# interacto.net
KiCad netlist of a schematic drawn in EAGLE
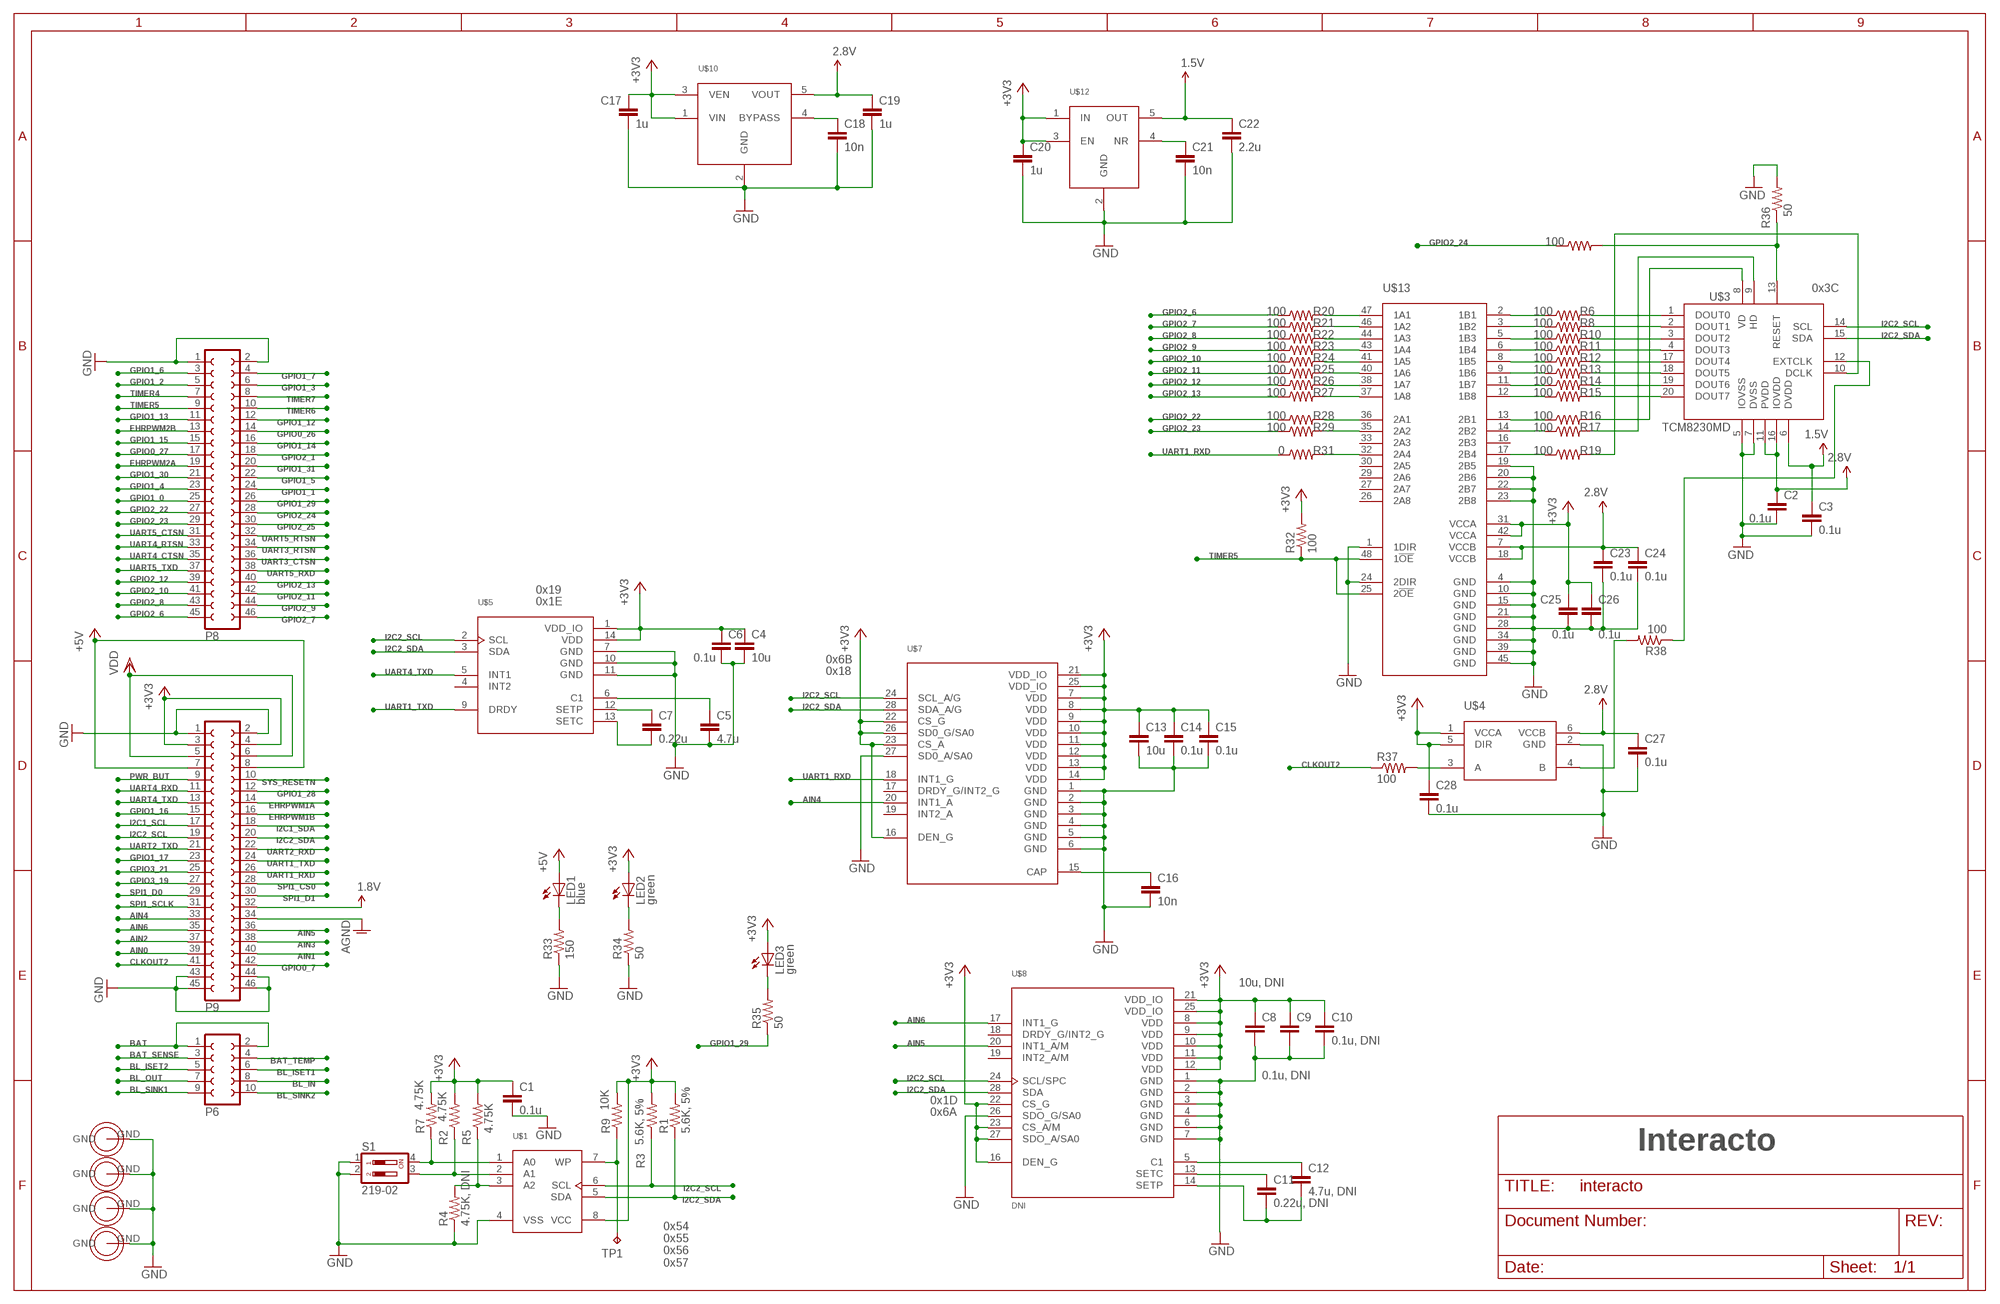
[diagram p0: schematic, sheet 1]

(export (version "E")
  (design (tool "Eeschema 10.0.6"))
  (components
    (comp (ref "C1")
      (value "0.1u")
      (footprint "eagle-import:C0603")
      (fields (field (name "MPN") "VJ0603V104ZXXCW1BC"))
      (libsource (lib "eagle-import") (part "C-EUC0603"))
    )
    (comp (ref "C2")
      (value "0.1u")
      (footprint "eagle-import:C0603")
      (fields (field (name "MPN") "VJ0603V104ZXXCW1BC"))
      (libsource (lib "eagle-import") (part "C-EUC0603"))
    )
    (comp (ref "C3")
      (value "0.1u")
      (footprint "eagle-import:C0603")
      (fields (field (name "MPN") "VJ0603V104ZXXCW1BC"))
      (libsource (lib "eagle-import") (part "C-EUC0603"))
    )
    (comp (ref "C4")
      (value "10u")
      (footprint "eagle-import:C0603")
      (fields (field (name "MPN") "LMK107BBJ106MALT"))
      (libsource (lib "eagle-import") (part "C-EUC0603"))
    )
    (comp (ref "C5")
      (value "4.7u")
      (footprint "eagle-import:C0603")
      (fields (field (name "MPN") "GRM188F51A475ZE20J"))
      (libsource (lib "eagle-import") (part "C-EUC0603"))
    )
    (comp (ref "C6")
      (value "0.1u")
      (footprint "eagle-import:C0603")
      (fields (field (name "MPN") "VJ0603V104ZXXCW1BC"))
      (libsource (lib "eagle-import") (part "C-EUC0603"))
    )
    (comp (ref "C7")
      (value "0.22u")
      (footprint "eagle-import:C0603")
      (fields (field (name "MPN") "VJ0603V224MXJPW1BC"))
      (libsource (lib "eagle-import") (part "C-EUC0603"))
    )
    (comp (ref "C8")
      (value "10u, DNI")
      (footprint "eagle-import:C0603")
      (fields (field (name "MPN") "LMK107BBJ106MALT"))
      (libsource (lib "eagle-import") (part "C-EUC0603"))
    )
    (comp (ref "C9")
      (value "0.1u, DNI")
      (footprint "eagle-import:C0603")
      (fields (field (name "MPN") "VJ0603V104ZXXCW1BC"))
      (libsource (lib "eagle-import") (part "C-EUC0603"))
    )
    (comp (ref "C10")
      (value "0.1u, DNI")
      (footprint "eagle-import:C0603")
      (fields (field (name "MPN") "VJ0603V104ZXXCW1BC"))
      (libsource (lib "eagle-import") (part "C-EUC0603"))
    )
    (comp (ref "C11")
      (value "0.22u, DNI")
      (footprint "eagle-import:C0603")
      (fields (field (name "MPN") "VJ0603V224MXJPW1BC"))
      (libsource (lib "eagle-import") (part "C-EUC0603"))
    )
    (comp (ref "C12")
      (value "4.7u, DNI")
      (footprint "eagle-import:C0603")
      (fields (field (name "MPN") "GRM188F51A475ZE20J"))
      (libsource (lib "eagle-import") (part "C-EUC0603"))
    )
    (comp (ref "C13")
      (value "10u")
      (footprint "eagle-import:C0603")
      (fields (field (name "MPN") "LMK107BBJ106MALT"))
      (libsource (lib "eagle-import") (part "C-EUC0603"))
    )
    (comp (ref "C14")
      (value "0.1u")
      (footprint "eagle-import:C0603")
      (fields (field (name "MPN") "VJ0603V104ZXXCW1BC"))
      (libsource (lib "eagle-import") (part "C-EUC0603"))
    )
    (comp (ref "C15")
      (value "0.1u")
      (footprint "eagle-import:C0603")
      (fields (field (name "MPN") "VJ0603V104ZXXCW1BC"))
      (libsource (lib "eagle-import") (part "C-EUC0603"))
    )
    (comp (ref "C16")
      (value "10n")
      (footprint "eagle-import:C0603")
      (fields (field (name "MPN") "VJ0603Y103KXACW1BC"))
      (libsource (lib "eagle-import") (part "C-EUC0603"))
    )
    (comp (ref "C17")
      (value "1u")
      (footprint "eagle-import:C0603")
      (fields (field (name "MPN") "C1608X7R1C105K"))
      (libsource (lib "eagle-import") (part "C-EUC0603"))
    )
    (comp (ref "C18")
      (value "10n")
      (footprint "eagle-import:C0603")
      (fields (field (name "MPN") "VJ0603Y103KXACW1BC"))
      (libsource (lib "eagle-import") (part "C-EUC0603"))
    )
    (comp (ref "C19")
      (value "1u")
      (footprint "eagle-import:C0603")
      (fields (field (name "MPN") "C1608X7R1C105K"))
      (libsource (lib "eagle-import") (part "C-EUC0603"))
    )
    (comp (ref "C20")
      (value "1u")
      (footprint "eagle-import:C0603")
      (fields (field (name "MPN") "C1608X7R1C105K"))
      (libsource (lib "eagle-import") (part "C-EUC0603"))
    )
    (comp (ref "C21")
      (value "10n")
      (footprint "eagle-import:C0603")
      (fields (field (name "MPN") "VJ0603Y103KXACW1BC"))
      (libsource (lib "eagle-import") (part "C-EUC0603"))
    )
    (comp (ref "C22")
      (value "2.2u")
      (footprint "eagle-import:C0603")
      (fields (field (name "MPN") "C1608Y5V1C225Z"))
      (libsource (lib "eagle-import") (part "C-EUC0603"))
    )
    (comp (ref "C23")
      (value "0.1u")
      (footprint "eagle-import:C0603")
      (fields (field (name "MPN") "VJ0603V104ZXXCW1BC"))
      (libsource (lib "eagle-import") (part "C-EUC0603"))
    )
    (comp (ref "C24")
      (value "0.1u")
      (footprint "eagle-import:C0603")
      (fields (field (name "MPN") "VJ0603V104ZXXCW1BC"))
      (libsource (lib "eagle-import") (part "C-EUC0603"))
    )
    (comp (ref "C25")
      (value "0.1u")
      (footprint "eagle-import:C0603")
      (fields (field (name "MPN") "VJ0603V104ZXXCW1BC"))
      (libsource (lib "eagle-import") (part "C-EUC0603"))
    )
    (comp (ref "C26")
      (value "0.1u")
      (footprint "eagle-import:C0603")
      (fields (field (name "MPN") "VJ0603V104ZXXCW1BC"))
      (libsource (lib "eagle-import") (part "C-EUC0603"))
    )
    (comp (ref "C27")
      (value "0.1u")
      (footprint "eagle-import:C0603")
      (fields (field (name "MPN") "VJ0603V104ZXXCW1BC"))
      (libsource (lib "eagle-import") (part "C-EUC0603"))
    )
    (comp (ref "C28")
      (value "0.1u")
      (footprint "eagle-import:C0603")
      (fields (field (name "MPN") "VJ0603V104ZXXCW1BC"))
      (libsource (lib "eagle-import") (part "C-EUC0603"))
    )
    (comp (ref "H1")
      (value "HOLE")
      (footprint "eagle-import:HOLE")
      (libsource (lib "eagle-import") (part "HOLE"))
    )
    (comp (ref "H2")
      (value "HOLE")
      (footprint "eagle-import:HOLE")
      (libsource (lib "eagle-import") (part "HOLE"))
    )
    (comp (ref "H3")
      (value "HOLE")
      (footprint "eagle-import:HOLE")
      (libsource (lib "eagle-import") (part "HOLE"))
    )
    (comp (ref "H4")
      (value "HOLE")
      (footprint "eagle-import:HOLE")
      (libsource (lib "eagle-import") (part "HOLE"))
    )
    (comp (ref "LED1")
      (value "blue")
      (footprint "eagle-import:CHIPLED_0603")
      (fields (field (name "MPN") "HT-193NB-5589"))
      (libsource (lib "eagle-import") (part "LEDCHIPLED_0603"))
    )
    (comp (ref "LED2")
      (value "green")
      (footprint "eagle-import:CHIPLED_0603")
      (fields (field (name "MPN") "LG Q971-KN-1"))
      (libsource (lib "eagle-import") (part "LEDCHIPLED_0603"))
    )
    (comp (ref "LED3")
      (value "green")
      (footprint "eagle-import:CHIPLED_0603")
      (fields (field (name "MPN") "LG Q971-KN-1"))
      (libsource (lib "eagle-import") (part "LEDCHIPLED_0603"))
    )
    (comp (ref "P6")
      (value "FE05-2")
      (footprint "eagle-import:FE05-2")
      (fields (field (name "MPN") "SSHQ-105-D-10-GT-LF "))
      (libsource (lib "eagle-import") (part "FE05-2"))
    )
    (comp (ref "P8")
      (value "FE23-2")
      (footprint "eagle-import:FE23-2")
      (fields (field (name "MPN") "SSHQ-123-D-10-GT-LF "))
      (libsource (lib "eagle-import") (part "FE23-2"))
    )
    (comp (ref "P9")
      (value "FE23-2")
      (footprint "eagle-import:FE23-2")
      (fields (field (name "MPN") "SSHQ-123-D-10-GT-LF "))
      (libsource (lib "eagle-import") (part "FE23-2"))
    )
    (comp (ref "R1")
      (value "5.6K, 5%")
      (footprint "eagle-import:R0603")
      (fields (field (name "MPN") "RK73B1JTTDD562J"))
      (libsource (lib "eagle-import") (part "R-US_R0603"))
    )
    (comp (ref "R2")
      (value "4.75K")
      (footprint "eagle-import:R0603")
      (fields (field (name "MPN") "CR0603-FX-4751GLF"))
      (libsource (lib "eagle-import") (part "R-US_R0603"))
    )
    (comp (ref "R3")
      (value "5.6K, 5%")
      (footprint "eagle-import:R0603")
      (fields (field (name "MPN") "RK73B1JTTDD562J"))
      (libsource (lib "eagle-import") (part "R-US_R0603"))
    )
    (comp (ref "R4")
      (value "4.75K, DNI")
      (footprint "eagle-import:R0603")
      (fields (field (name "MPN") "CR0603-FX-4751GLF"))
      (libsource (lib "eagle-import") (part "R-US_R0603"))
    )
    (comp (ref "R5")
      (value "4.75K")
      (footprint "eagle-import:R0603")
      (fields (field (name "MPN") "CR0603-FX-4751GLF"))
      (libsource (lib "eagle-import") (part "R-US_R0603"))
    )
    (comp (ref "R6")
      (value "100")
      (footprint "eagle-import:R0402")
      (fields (field (name "MPN") "ERA-6AED101V"))
      (libsource (lib "eagle-import") (part "R-US_R0402"))
    )
    (comp (ref "R7")
      (value "4.75K")
      (footprint "eagle-import:R0603")
      (fields (field (name "MPN") "CR0603-FX-4751GLF"))
      (libsource (lib "eagle-import") (part "R-US_R0603"))
    )
    (comp (ref "R8")
      (value "100")
      (footprint "eagle-import:R0402")
      (fields (field (name "MPN") "ERA-6AED101V"))
      (libsource (lib "eagle-import") (part "R-US_R0402"))
    )
    (comp (ref "R9")
      (value "10K")
      (footprint "eagle-import:R0603")
      (fields (field (name "MPN") "WR06X1002FTL"))
      (libsource (lib "eagle-import") (part "R-US_R0603"))
    )
    (comp (ref "R10")
      (value "100")
      (footprint "eagle-import:R0402")
      (fields (field (name "MPN") "ERA-6AED101V"))
      (libsource (lib "eagle-import") (part "R-US_R0402"))
    )
    (comp (ref "R11")
      (value "100")
      (footprint "eagle-import:R0402")
      (fields (field (name "MPN") "ERA-6AED101V"))
      (libsource (lib "eagle-import") (part "R-US_R0402"))
    )
    (comp (ref "R12")
      (value "100")
      (footprint "eagle-import:R0402")
      (fields (field (name "MPN") "ERA-6AED101V"))
      (libsource (lib "eagle-import") (part "R-US_R0402"))
    )
    (comp (ref "R13")
      (value "100")
      (footprint "eagle-import:R0402")
      (fields (field (name "MPN") "ERA-6AED101V"))
      (libsource (lib "eagle-import") (part "R-US_R0402"))
    )
    (comp (ref "R14")
      (value "100")
      (footprint "eagle-import:R0402")
      (fields (field (name "MPN") "ERA-6AED101V"))
      (libsource (lib "eagle-import") (part "R-US_R0402"))
    )
    (comp (ref "R15")
      (value "100")
      (footprint "eagle-import:R0402")
      (fields (field (name "MPN") "ERA-6AED101V"))
      (libsource (lib "eagle-import") (part "R-US_R0402"))
    )
    (comp (ref "R16")
      (value "100")
      (footprint "eagle-import:R0402")
      (fields (field (name "MPN") "ERA-6AED101V"))
      (libsource (lib "eagle-import") (part "R-US_R0402"))
    )
    (comp (ref "R17")
      (value "100")
      (footprint "eagle-import:R0402")
      (fields (field (name "MPN") "ERA-6AED101V"))
      (libsource (lib "eagle-import") (part "R-US_R0402"))
    )
    (comp (ref "R18")
      (value "100")
      (footprint "eagle-import:R0402")
      (fields (field (name "MPN") "ERA-6AED101V"))
      (libsource (lib "eagle-import") (part "R-US_R0402"))
    )
    (comp (ref "R19")
      (value "100")
      (footprint "eagle-import:R0402")
      (fields (field (name "MPN") "ERA-6AED101V"))
      (libsource (lib "eagle-import") (part "R-US_R0402"))
    )
    (comp (ref "R20")
      (value "100")
      (footprint "eagle-import:R0402")
      (fields (field (name "MPN") "ERA-6AED101V"))
      (libsource (lib "eagle-import") (part "R-US_R0402"))
    )
    (comp (ref "R21")
      (value "100")
      (footprint "eagle-import:R0402")
      (fields (field (name "MPN") "ERA-6AED101V"))
      (libsource (lib "eagle-import") (part "R-US_R0402"))
    )
    (comp (ref "R22")
      (value "100")
      (footprint "eagle-import:R0402")
      (fields (field (name "MPN") "ERA-6AED101V"))
      (libsource (lib "eagle-import") (part "R-US_R0402"))
    )
    (comp (ref "R23")
      (value "100")
      (footprint "eagle-import:R0402")
      (fields (field (name "MPN") "ERA-6AED101V"))
      (libsource (lib "eagle-import") (part "R-US_R0402"))
    )
    (comp (ref "R24")
      (value "100")
      (footprint "eagle-import:R0402")
      (fields (field (name "MPN") "ERA-6AED101V"))
      (libsource (lib "eagle-import") (part "R-US_R0402"))
    )
    (comp (ref "R25")
      (value "100")
      (footprint "eagle-import:R0402")
      (fields (field (name "MPN") "ERA-6AED101V"))
      (libsource (lib "eagle-import") (part "R-US_R0402"))
    )
    (comp (ref "R26")
      (value "100")
      (footprint "eagle-import:R0402")
      (fields (field (name "MPN") "ERA-6AED101V"))
      (libsource (lib "eagle-import") (part "R-US_R0402"))
    )
    (comp (ref "R27")
      (value "100")
      (footprint "eagle-import:R0402")
      (fields (field (name "MPN") "CR0402-JW-330GLF"))
      (libsource (lib "eagle-import") (part "R-US_R0402"))
    )
    (comp (ref "R28")
      (value "100")
      (footprint "eagle-import:R0402")
      (fields (field (name "MPN") "ERA-6AED101V"))
      (libsource (lib "eagle-import") (part "R-US_R0402"))
    )
    (comp (ref "R29")
      (value "100")
      (footprint "eagle-import:R0402")
      (fields (field (name "MPN") "ERA-6AED101V"))
      (libsource (lib "eagle-import") (part "R-US_R0402"))
    )
    (comp (ref "R31")
      (value "0")
      (footprint "eagle-import:R0402")
      (fields (field (name "MPN") "ERJ-2GE0R00X"))
      (libsource (lib "eagle-import") (part "R-US_R0402"))
    )
    (comp (ref "R32")
      (value "100")
      (footprint "eagle-import:R0402")
      (fields (field (name "MPN") "ERA-6AED101V"))
      (libsource (lib "eagle-import") (part "R-US_R0402"))
    )
    (comp (ref "R33")
      (value "150")
      (footprint "eagle-import:R0603")
      (fields (field (name "MPN") "302-150-RC"))
      (libsource (lib "eagle-import") (part "R-US_R0603"))
    )
    (comp (ref "R34")
      (value "50")
      (footprint "eagle-import:R0603")
      (fields (field (name "MPN") "302-49.9-RC"))
      (libsource (lib "eagle-import") (part "R-US_R0603"))
    )
    (comp (ref "R35")
      (value "50")
      (footprint "eagle-import:R0603")
      (fields (field (name "MPN") "302-49.9-RC"))
      (libsource (lib "eagle-import") (part "R-US_R0603"))
    )
    (comp (ref "R36")
      (value "50")
      (footprint "eagle-import:R0402")
      (fields (field (name "MPN") "302-49.9-RC"))
      (libsource (lib "eagle-import") (part "R-US_R0402"))
    )
    (comp (ref "R37")
      (value "100")
      (footprint "eagle-import:R0402")
      (fields (field (name "MPN") "ERA-6AED101V"))
      (libsource (lib "eagle-import") (part "R-US_R0402"))
    )
    (comp (ref "R38")
      (value "100")
      (footprint "eagle-import:R0402")
      (fields (field (name "MPN") "ERA-6AED101V"))
      (libsource (lib "eagle-import") (part "R-US_R0402"))
    )
    (comp (ref "S1")
      (value "219-02")
      (footprint "eagle-import:CTS-219-02")
      (fields (field (name "MPN") "219-2MST"))
      (libsource (lib "eagle-import") (part "219-02"))
    )
    (comp (ref "TP1")
      (value "TPB2,54")
      (footprint "eagle-import:B2,54")
      (libsource (lib "eagle-import") (part "TPB2,54"))
    )
    (comp (ref "U$1")
      (value "CAT24C256")
      (footprint "eagle-import:SOIC8")
      (fields (field (name "MPN") "CAT24C256WI-GT3"))
      (libsource (lib "eagle-import") (part "CAT24C256"))
    )
    (comp (ref "U$3")
      (value "TCM8230MD")
      (footprint "eagle-import:TCM8230MD")
      (libsource (lib "eagle-import") (part "TCM8230MD"))
    )
    (comp (ref "U$4")
      (value "SN74LVC1T45")
      (footprint "eagle-import:SOT23-6")
      (fields (field (name "MPN") "SN74LVC1T45DBVR"))
      (libsource (lib "eagle-import") (part "SN74LVC1T45"))
    )
    (comp (ref "U$5")
      (value "LSM303DLHC")
      (footprint "eagle-import:LGA14")
      (libsource (lib "eagle-import") (part "LSM303DLHC"))
    )
    (comp (ref "U$7")
      (value "LSM330DLC")
      (footprint "eagle-import:LGA28-4X5")
      (libsource (lib "eagle-import") (part "LSM330DLC"))
    )
    (comp (ref "U$8")
      (value "DNI")
      (footprint "eagle-import:LGA28")
      (fields (field (name "MPN") "LSM333D"))
      (libsource (lib "eagle-import") (part "LSM333D"))
    )
    (comp (ref "U$10")
      (value "LP3985")
      (footprint "eagle-import:SOT23-5")
      (fields (field (name "MPN") "LP3985IM5-2.8/NOPB"))
      (libsource (lib "eagle-import") (part "LP3985"))
    )
    (comp (ref "U$12")
      (value "TPS799XX")
      (footprint "eagle-import:SOT23-5")
      (fields (field (name "MPN") "TPS79915DDCR"))
      (libsource (lib "eagle-import") (part "TPS799XX"))
    )
    (comp (ref "U$13")
      (value "SN74LVCH16T245")
      (footprint "eagle-import:TSSOP48")
      (fields (field (name "MPN") "SN74LVCH16T245DGGR"))
      (libsource (lib "eagle-import") (part "SN74LVCH16T245"))
    )
  )
  (nets
    (net (code "1") (name "+3V3") (class "Default")
      (node (ref "C1") (pin "1") (pinfunction "1_1") (pintype "passive"))
      (node (ref "C10") (pin "1") (pinfunction "1_1") (pintype "passive"))
      (node (ref "C13") (pin "1") (pinfunction "1_1") (pintype "passive"))
      (node (ref "C14") (pin "1") (pinfunction "1_1") (pintype "passive"))
      (node (ref "C15") (pin "1") (pinfunction "1_1") (pintype "passive"))
      (node (ref "C17") (pin "1") (pinfunction "1_1") (pintype "passive"))
      (node (ref "C20") (pin "1") (pinfunction "1_1") (pintype "passive"))
      (node (ref "C25") (pin "1") (pinfunction "1_1") (pintype "passive"))
      (node (ref "C26") (pin "1") (pinfunction "1_1") (pintype "passive"))
      (node (ref "C28") (pin "1") (pinfunction "1_1") (pintype "passive"))
      (node (ref "C4") (pin "1") (pinfunction "1_1") (pintype "passive"))
      (node (ref "C6") (pin "1") (pinfunction "1_1") (pintype "passive"))
      (node (ref "C8") (pin "1") (pinfunction "1_1") (pintype "passive"))
      (node (ref "C9") (pin "1") (pinfunction "1_1") (pintype "passive"))
      (node (ref "LED2") (pin "A") (pinfunction "A_A") (pintype "passive"))
      (node (ref "LED3") (pin "A") (pinfunction "A_A") (pintype "passive"))
      (node (ref "P9") (pin "3") (pinfunction "3_3") (pintype "passive"))
      (node (ref "P9") (pin "4") (pinfunction "4_4") (pintype "passive"))
      (node (ref "R1") (pin "2") (pinfunction "2_2") (pintype "passive"))
      (node (ref "R2") (pin "2") (pinfunction "2_2") (pintype "passive"))
      (node (ref "R3") (pin "2") (pinfunction "2_2") (pintype "passive"))
      (node (ref "R32") (pin "2") (pinfunction "2_2") (pintype "passive"))
      (node (ref "R5") (pin "2") (pinfunction "2_2") (pintype "passive"))
      (node (ref "R7") (pin "2") (pinfunction "2_2") (pintype "passive"))
      (node (ref "R9") (pin "2") (pinfunction "2_2") (pintype "passive"))
      (node (ref "U$1") (pin "8") (pinfunction "VCC_8") (pintype "power_in"))
      (node (ref "U$10") (pin "1") (pinfunction "VIN_1") (pintype "power_in"))
      (node (ref "U$10") (pin "3") (pinfunction "VEN_3") (pintype "input"))
      (node (ref "U$12") (pin "1") (pinfunction "IN_1") (pintype "power_in"))
      (node (ref "U$12") (pin "3") (pinfunction "EN_3") (pintype "input"))
      (node (ref "U$13") (pin "31") (pinfunction "VCCA_31") (pintype "power_in"))
      (node (ref "U$13") (pin "42") (pinfunction "VCCA_42") (pintype "power_in"))
      (node (ref "U$4") (pin "1") (pinfunction "VCCA_1") (pintype "power_in"))
      (node (ref "U$4") (pin "5") (pinfunction "DIR_5") (pintype "input"))
      (node (ref "U$5") (pin "1") (pinfunction "VDD_IO_1") (pintype "power_in"))
      (node (ref "U$5") (pin "14") (pinfunction "VDD_14") (pintype "power_in"))
      (node (ref "U$7") (pin "10") (pinfunction "VDD_10") (pintype "power_in"))
      (node (ref "U$7") (pin "11") (pinfunction "VDD_11") (pintype "power_in"))
      (node (ref "U$7") (pin "12") (pinfunction "VDD_12") (pintype "power_in"))
      (node (ref "U$7") (pin "13") (pinfunction "VDD_13") (pintype "power_in"))
      (node (ref "U$7") (pin "14") (pinfunction "VDD_14") (pintype "power_in"))
      (node (ref "U$7") (pin "16") (pinfunction "DEN_G_16") (pintype "input"))
      (node (ref "U$7") (pin "21") (pinfunction "VDD_IO_21") (pintype "power_in"))
      (node (ref "U$7") (pin "22") (pinfunction "CS_G_22") (pintype "input"))
      (node (ref "U$7") (pin "23") (pinfunction "CS_A_23") (pintype "input"))
      (node (ref "U$7") (pin "25") (pinfunction "VDD_IO_25") (pintype "power_in"))
      (node (ref "U$7") (pin "26") (pinfunction "SD0_G/SA0_26") (pintype "bidirectional"))
      (node (ref "U$7") (pin "7") (pinfunction "VDD_7") (pintype "power_in"))
      (node (ref "U$7") (pin "8") (pinfunction "VDD_8") (pintype "power_in"))
      (node (ref "U$7") (pin "9") (pinfunction "VDD_9") (pintype "power_in"))
      (node (ref "U$8") (pin "10") (pinfunction "VDD_10") (pintype "power_in"))
      (node (ref "U$8") (pin "11") (pinfunction "VDD_11") (pintype "power_in"))
      (node (ref "U$8") (pin "12") (pinfunction "VDD_12") (pintype "power_in"))
      (node (ref "U$8") (pin "16") (pinfunction "DEN_G_16") (pintype "input"))
      (node (ref "U$8") (pin "21") (pinfunction "VDD_IO_21") (pintype "power_in"))
      (node (ref "U$8") (pin "22") (pinfunction "CS_G_22") (pintype "input"))
      (node (ref "U$8") (pin "23") (pinfunction "CS_A/M_23") (pintype "input"))
      (node (ref "U$8") (pin "25") (pinfunction "VDD_IO_25") (pintype "power_in"))
      (node (ref "U$8") (pin "27") (pinfunction "SDO_A/SA0_27") (pintype "bidirectional"))
      (node (ref "U$8") (pin "8") (pinfunction "VDD_8") (pintype "power_in"))
      (node (ref "U$8") (pin "9") (pinfunction "VDD_9") (pintype "power_in"))
    )
    (net (code "2") (name "+5V") (class "Default")
      (node (ref "LED1") (pin "A") (pinfunction "A_A") (pintype "passive"))
      (node (ref "P9") (pin "7") (pinfunction "7_7") (pintype "passive"))
      (node (ref "P9") (pin "8") (pinfunction "8_8") (pintype "passive"))
    )
    (net (code "3") (name "/AIN0") (class "Default")
      (node (ref "P9") (pin "39") (pinfunction "39_39") (pintype "passive"))
    )
    (net (code "4") (name "/AIN1") (class "Default")
      (node (ref "P9") (pin "40") (pinfunction "40_40") (pintype "passive"))
    )
    (net (code "5") (name "/AIN2") (class "Default")
      (node (ref "P9") (pin "37") (pinfunction "37_37") (pintype "passive"))
    )
    (net (code "6") (name "/AIN3") (class "Default")
      (node (ref "P9") (pin "38") (pinfunction "38_38") (pintype "passive"))
    )
    (net (code "7") (name "/AIN4") (class "Default")
      (node (ref "P9") (pin "33") (pinfunction "33_33") (pintype "passive"))
      (node (ref "U$7") (pin "20") (pinfunction "INT1_A_20") (pintype "output"))
    )
    (net (code "8") (name "/AIN5") (class "Default")
      (node (ref "P9") (pin "36") (pinfunction "36_36") (pintype "passive"))
      (node (ref "U$8") (pin "20") (pinfunction "INT1_A/M_20") (pintype "output"))
    )
    (net (code "9") (name "/AIN6") (class "Default")
      (node (ref "P9") (pin "35") (pinfunction "35_35") (pintype "passive"))
      (node (ref "U$8") (pin "17") (pinfunction "INT1_G_17") (pintype "output"))
    )
    (net (code "10") (name "/BAT") (class "Default")
      (node (ref "P6") (pin "1") (pinfunction "1_1") (pintype "passive"))
      (node (ref "P6") (pin "2") (pinfunction "2_2") (pintype "passive"))
    )
    (net (code "11") (name "/BAT_SENSE") (class "Default")
      (node (ref "P6") (pin "3") (pinfunction "3_3") (pintype "passive"))
    )
    (net (code "12") (name "/BAT_TEMP") (class "Default")
      (node (ref "P6") (pin "4") (pinfunction "4_4") (pintype "passive"))
    )
    (net (code "13") (name "/BL_IN") (class "Default")
      (node (ref "P6") (pin "8") (pinfunction "8_8") (pintype "passive"))
    )
    (net (code "14") (name "/BL_ISET1") (class "Default")
      (node (ref "P6") (pin "6") (pinfunction "6_6") (pintype "passive"))
    )
    (net (code "15") (name "/BL_ISET2") (class "Default")
      (node (ref "P6") (pin "5") (pinfunction "5_5") (pintype "passive"))
    )
    (net (code "16") (name "/BL_OUT") (class "Default")
      (node (ref "P6") (pin "7") (pinfunction "7_7") (pintype "passive"))
    )
    (net (code "17") (name "/BL_SINK1") (class "Default")
      (node (ref "P6") (pin "9") (pinfunction "9_9") (pintype "passive"))
    )
    (net (code "18") (name "/BL_SINK2") (class "Default")
      (node (ref "P6") (pin "10") (pinfunction "10_10") (pintype "passive"))
    )
    (net (code "19") (name "/CLKOUT2") (class "Default")
      (node (ref "P9") (pin "41") (pinfunction "41_41") (pintype "passive"))
      (node (ref "R37") (pin "1") (pinfunction "1_1") (pintype "passive"))
    )
    (net (code "20") (name "/EHRPWM1A") (class "Default")
      (node (ref "P9") (pin "14") (pinfunction "14_14") (pintype "passive"))
    )
    (net (code "21") (name "/EHRPWM1B") (class "Default")
      (node (ref "P9") (pin "16") (pinfunction "16_16") (pintype "passive"))
    )
    (net (code "22") (name "/EHRPWM2A") (class "Default")
      (node (ref "P8") (pin "19") (pinfunction "19_19") (pintype "passive"))
    )
    (net (code "23") (name "/EHRPWM2B") (class "Default")
      (node (ref "P8") (pin "13") (pinfunction "13_13") (pintype "passive"))
    )
    (net (code "24") (name "/GPIO0_7") (class "Default")
      (node (ref "P9") (pin "42") (pinfunction "42_42") (pintype "passive"))
    )
    (net (code "25") (name "/GPIO0_26") (class "Default")
      (node (ref "P8") (pin "14") (pinfunction "14_14") (pintype "passive"))
    )
    (net (code "26") (name "/GPIO0_27") (class "Default")
      (node (ref "P8") (pin "17") (pinfunction "17_17") (pintype "passive"))
    )
    (net (code "27") (name "/GPIO1_0") (class "Default")
      (node (ref "P8") (pin "25") (pinfunction "25_25") (pintype "passive"))
    )
    (net (code "28") (name "/GPIO1_1") (class "Default")
      (node (ref "P8") (pin "24") (pinfunction "24_24") (pintype "passive"))
    )
    (net (code "29") (name "/GPIO1_2") (class "Default")
      (node (ref "P8") (pin "5") (pinfunction "5_5") (pintype "passive"))
    )
    (net (code "30") (name "/GPIO1_3") (class "Default")
      (node (ref "P8") (pin "6") (pinfunction "6_6") (pintype "passive"))
    )
    (net (code "31") (name "/GPIO1_4") (class "Default")
      (node (ref "P8") (pin "23") (pinfunction "23_23") (pintype "passive"))
    )
    (net (code "32") (name "/GPIO1_5") (class "Default")
      (node (ref "P8") (pin "22") (pinfunction "22_22") (pintype "passive"))
    )
    (net (code "33") (name "/GPIO1_6") (class "Default")
      (node (ref "P8") (pin "3") (pinfunction "3_3") (pintype "passive"))
    )
    (net (code "34") (name "/GPIO1_7") (class "Default")
      (node (ref "P8") (pin "4") (pinfunction "4_4") (pintype "passive"))
    )
    (net (code "35") (name "/GPIO1_12") (class "Default")
      (node (ref "P8") (pin "12") (pinfunction "12_12") (pintype "passive"))
    )
    (net (code "36") (name "/GPIO1_13") (class "Default")
      (node (ref "P8") (pin "11") (pinfunction "11_11") (pintype "passive"))
    )
    (net (code "37") (name "/GPIO1_14") (class "Default")
      (node (ref "P8") (pin "16") (pinfunction "16_16") (pintype "passive"))
    )
    (net (code "38") (name "/GPIO1_15") (class "Default")
      (node (ref "P8") (pin "15") (pinfunction "15_15") (pintype "passive"))
    )
    (net (code "39") (name "/GPIO1_16") (class "Default")
      (node (ref "P9") (pin "15") (pinfunction "15_15") (pintype "passive"))
    )
    (net (code "40") (name "/GPIO1_17") (class "Default")
      (node (ref "P9") (pin "23") (pinfunction "23_23") (pintype "passive"))
    )
    (net (code "41") (name "/GPIO1_28") (class "Default")
      (node (ref "P9") (pin "12") (pinfunction "12_12") (pintype "passive"))
    )
    (net (code "42") (name "/GPIO1_29") (class "Default")
      (node (ref "P8") (pin "26") (pinfunction "26_26") (pintype "passive"))
      (node (ref "R35") (pin "1") (pinfunction "1_1") (pintype "passive"))
    )
    (net (code "43") (name "/GPIO1_30") (class "Default")
      (node (ref "P8") (pin "21") (pinfunction "21_21") (pintype "passive"))
    )
    (net (code "44") (name "/GPIO1_31") (class "Default")
      (node (ref "P8") (pin "20") (pinfunction "20_20") (pintype "passive"))
    )
    (net (code "45") (name "/GPIO2_1") (class "Default")
      (node (ref "P8") (pin "18") (pinfunction "18_18") (pintype "passive"))
    )
    (net (code "46") (name "/GPIO2_6") (class "Default")
      (node (ref "P8") (pin "45") (pinfunction "45_45") (pintype "passive"))
      (node (ref "R20") (pin "1") (pinfunction "1_1") (pintype "passive"))
    )
    (net (code "47") (name "/GPIO2_7") (class "Default")
      (node (ref "P8") (pin "46") (pinfunction "46_46") (pintype "passive"))
      (node (ref "R21") (pin "1") (pinfunction "1_1") (pintype "passive"))
    )
    (net (code "48") (name "/GPIO2_8") (class "Default")
      (node (ref "P8") (pin "43") (pinfunction "43_43") (pintype "passive"))
      (node (ref "R22") (pin "1") (pinfunction "1_1") (pintype "passive"))
    )
    (net (code "49") (name "/GPIO2_9") (class "Default")
      (node (ref "P8") (pin "44") (pinfunction "44_44") (pintype "passive"))
      (node (ref "R23") (pin "1") (pinfunction "1_1") (pintype "passive"))
    )
    (net (code "50") (name "/GPIO2_10") (class "Default")
      (node (ref "P8") (pin "41") (pinfunction "41_41") (pintype "passive"))
      (node (ref "R24") (pin "1") (pinfunction "1_1") (pintype "passive"))
    )
    (net (code "51") (name "/GPIO2_11") (class "Default")
      (node (ref "P8") (pin "42") (pinfunction "42_42") (pintype "passive"))
      (node (ref "R25") (pin "1") (pinfunction "1_1") (pintype "passive"))
    )
    (net (code "52") (name "/GPIO2_12") (class "Default")
      (node (ref "P8") (pin "39") (pinfunction "39_39") (pintype "passive"))
      (node (ref "R26") (pin "1") (pinfunction "1_1") (pintype "passive"))
    )
    (net (code "53") (name "/GPIO2_13") (class "Default")
      (node (ref "P8") (pin "40") (pinfunction "40_40") (pintype "passive"))
      (node (ref "R27") (pin "1") (pinfunction "1_1") (pintype "passive"))
    )
    (net (code "54") (name "/GPIO2_22") (class "Default")
      (node (ref "P8") (pin "27") (pinfunction "27_27") (pintype "passive"))
      (node (ref "R28") (pin "1") (pinfunction "1_1") (pintype "passive"))
    )
    (net (code "55") (name "/GPIO2_23") (class "Default")
      (node (ref "P8") (pin "29") (pinfunction "29_29") (pintype "passive"))
      (node (ref "R29") (pin "1") (pinfunction "1_1") (pintype "passive"))
    )
    (net (code "56") (name "/GPIO2_24") (class "Default")
      (node (ref "P8") (pin "28") (pinfunction "28_28") (pintype "passive"))
      (node (ref "R18") (pin "1") (pinfunction "1_1") (pintype "passive"))
    )
    (net (code "57") (name "/GPIO2_25") (class "Default")
      (node (ref "P8") (pin "30") (pinfunction "30_30") (pintype "passive"))
    )
    (net (code "58") (name "/GPIO3_19") (class "Default")
      (node (ref "P9") (pin "27") (pinfunction "27_27") (pintype "passive"))
    )
    (net (code "59") (name "/GPIO3_21") (class "Default")
      (node (ref "P9") (pin "25") (pinfunction "25_25") (pintype "passive"))
    )
    (net (code "60") (name "/I2C1_SCL") (class "Default")
      (node (ref "P9") (pin "17") (pinfunction "17_17") (pintype "passive"))
    )
    (net (code "61") (name "/I2C1_SDA") (class "Default")
      (node (ref "P9") (pin "18") (pinfunction "18_18") (pintype "passive"))
    )
    (net (code "62") (name "/I2C2_SCL") (class "Default")
      (node (ref "P9") (pin "19") (pinfunction "19_19") (pintype "passive"))
      (node (ref "R3") (pin "1") (pinfunction "1_1") (pintype "passive"))
      (node (ref "U$1") (pin "6") (pinfunction "SCL_6") (pintype "open_collector"))
      (node (ref "U$3") (pin "14") (pinfunction "SCL_14") (pintype "bidirectional"))
      (node (ref "U$5") (pin "2") (pinfunction "SCL_2") (pintype "open_collector"))
      (node (ref "U$7") (pin "24") (pinfunction "SCL_A/G_24") (pintype "open_collector"))
      (node (ref "U$8") (pin "24") (pinfunction "SCL/SPC_24") (pintype "open_collector"))
    )
    (net (code "63") (name "/I2C2_SDA") (class "Default")
      (node (ref "P9") (pin "20") (pinfunction "20_20") (pintype "passive"))
      (node (ref "R1") (pin "1") (pinfunction "1_1") (pintype "passive"))
      (node (ref "U$1") (pin "5") (pinfunction "SDA_5") (pintype "open_collector"))
      (node (ref "U$3") (pin "15") (pinfunction "SDA_15") (pintype "bidirectional"))
      (node (ref "U$5") (pin "3") (pinfunction "SDA_3") (pintype "open_collector"))
      (node (ref "U$7") (pin "28") (pinfunction "SDA_A/G_28") (pintype "open_collector"))
      (node (ref "U$8") (pin "28") (pinfunction "SDA_28") (pintype "open_collector"))
    )
    (net (code "64") (name "/PWR_BUT") (class "Default")
      (node (ref "P9") (pin "9") (pinfunction "9_9") (pintype "passive"))
    )
    (net (code "65") (name "/SPI1_CS0") (class "Default")
      (node (ref "P9") (pin "28") (pinfunction "28_28") (pintype "passive"))
    )
    (net (code "66") (name "/SPI1_D0") (class "Default")
      (node (ref "P9") (pin "29") (pinfunction "29_29") (pintype "passive"))
    )
    (net (code "67") (name "/SPI1_D1") (class "Default")
      (node (ref "P9") (pin "30") (pinfunction "30_30") (pintype "passive"))
    )
    (net (code "68") (name "/SPI1_SCLK") (class "Default")
      (node (ref "P9") (pin "31") (pinfunction "31_31") (pintype "passive"))
    )
    (net (code "69") (name "/SYS_RESETN") (class "Default")
      (node (ref "P9") (pin "10") (pinfunction "10_10") (pintype "passive"))
    )
    (net (code "70") (name "/TIMER4") (class "Default")
      (node (ref "P8") (pin "7") (pinfunction "7_7") (pintype "passive"))
    )
    (net (code "71") (name "/TIMER5") (class "Default")
      (node (ref "P8") (pin "9") (pinfunction "9_9") (pintype "passive"))
      (node (ref "R32") (pin "1") (pinfunction "1_1") (pintype "passive"))
      (node (ref "U$13") (pin "25") (pinfunction "2~{OE}_25") (pintype "input"))
      (node (ref "U$13") (pin "48") (pinfunction "1~{OE}_48") (pintype "input"))
    )
    (net (code "72") (name "/TIMER6") (class "Default")
      (node (ref "P8") (pin "10") (pinfunction "10_10") (pintype "passive"))
    )
    (net (code "73") (name "/TIMER7") (class "Default")
      (node (ref "P8") (pin "8") (pinfunction "8_8") (pintype "passive"))
    )
    (net (code "74") (name "/UART1_RXD") (class "Default")
      (node (ref "P9") (pin "26") (pinfunction "26_26") (pintype "passive"))
      (node (ref "R31") (pin "1") (pinfunction "1_1") (pintype "passive"))
      (node (ref "U$7") (pin "18") (pinfunction "INT1_G_18") (pintype "output"))
    )
    (net (code "75") (name "/UART1_TXD") (class "Default")
      (node (ref "P9") (pin "24") (pinfunction "24_24") (pintype "passive"))
      (node (ref "U$5") (pin "9") (pinfunction "DRDY_9") (pintype "output"))
    )
    (net (code "76") (name "/UART2_RXD") (class "Default")
      (node (ref "P9") (pin "22") (pinfunction "22_22") (pintype "passive"))
    )
    (net (code "77") (name "/UART2_TXD") (class "Default")
      (node (ref "P9") (pin "21") (pinfunction "21_21") (pintype "passive"))
    )
    (net (code "78") (name "/UART3_CTSN") (class "Default")
      (node (ref "P8") (pin "36") (pinfunction "36_36") (pintype "passive"))
    )
    (net (code "79") (name "/UART3_RTSN") (class "Default")
      (node (ref "P8") (pin "34") (pinfunction "34_34") (pintype "passive"))
    )
    (net (code "80") (name "/UART4_CTSN") (class "Default")
      (node (ref "P8") (pin "35") (pinfunction "35_35") (pintype "passive"))
    )
    (net (code "81") (name "/UART4_RTSN") (class "Default")
      (node (ref "P8") (pin "33") (pinfunction "33_33") (pintype "passive"))
    )
    (net (code "82") (name "/UART4_RXD") (class "Default")
      (node (ref "P9") (pin "11") (pinfunction "11_11") (pintype "passive"))
    )
    (net (code "83") (name "/UART4_TXD") (class "Default")
      (node (ref "P9") (pin "13") (pinfunction "13_13") (pintype "passive"))
      (node (ref "U$5") (pin "5") (pinfunction "INT1_5") (pintype "output"))
    )
    (net (code "84") (name "/UART5_CTSN") (class "Default")
      (node (ref "P8") (pin "31") (pinfunction "31_31") (pintype "passive"))
    )
    (net (code "85") (name "/UART5_RTSN") (class "Default")
      (node (ref "P8") (pin "32") (pinfunction "32_32") (pintype "passive"))
    )
    (net (code "86") (name "/UART5_RXD") (class "Default")
      (node (ref "P8") (pin "38") (pinfunction "38_38") (pintype "passive"))
    )
    (net (code "87") (name "/UART5_TXD") (class "Default")
      (node (ref "P8") (pin "37") (pinfunction "37_37") (pintype "passive"))
    )
    (net (code "88") (name "1.5V") (class "Default")
      (node (ref "C22") (pin "1") (pinfunction "1_1") (pintype "passive"))
      (node (ref "C3") (pin "1") (pinfunction "1_1") (pintype "passive"))
      (node (ref "U$12") (pin "5") (pinfunction "OUT_5") (pintype "power_in"))
      (node (ref "U$3") (pin "6") (pinfunction "DVDD_6") (pintype "power_in"))
    )
    (net (code "89") (name "1.8V") (class "Default")
      (node (ref "P9") (pin "32") (pinfunction "32_32") (pintype "passive"))
    )
    (net (code "90") (name "2.8V") (class "Default")
      (node (ref "C19") (pin "1") (pinfunction "1_1") (pintype "passive"))
      (node (ref "C2") (pin "1") (pinfunction "1_1") (pintype "passive"))
      (node (ref "C23") (pin "1") (pinfunction "1_1") (pintype "passive"))
      (node (ref "C24") (pin "1") (pinfunction "1_1") (pintype "passive"))
      (node (ref "C27") (pin "1") (pinfunction "1_1") (pintype "passive"))
      (node (ref "U$10") (pin "5") (pinfunction "VOUT_5") (pintype "power_in"))
      (node (ref "U$13") (pin "18") (pinfunction "VCCB_18") (pintype "power_in"))
      (node (ref "U$13") (pin "7") (pinfunction "VCCB_7") (pintype "power_in"))
      (node (ref "U$3") (pin "11") (pinfunction "PVDD_11") (pintype "power_in"))
      (node (ref "U$3") (pin "16") (pinfunction "IOVDD_16") (pintype "power_in"))
      (node (ref "U$4") (pin "6") (pinfunction "VCCB_6") (pintype "power_in"))
    )
    (net (code "91") (name "AGND") (class "Default")
      (node (ref "P9") (pin "34") (pinfunction "34_34") (pintype "passive"))
    )
    (net (code "92") (name "GND") (class "Default")
      (node (ref "C1") (pin "2") (pinfunction "2_2") (pintype "passive"))
      (node (ref "C10") (pin "2") (pinfunction "2_2") (pintype "passive"))
      (node (ref "C13") (pin "2") (pinfunction "2_2") (pintype "passive"))
      (node (ref "C14") (pin "2") (pinfunction "2_2") (pintype "passive"))
      (node (ref "C15") (pin "2") (pinfunction "2_2") (pintype "passive"))
      (node (ref "C16") (pin "2") (pinfunction "2_2") (pintype "passive"))
      (node (ref "C17") (pin "2") (pinfunction "2_2") (pintype "passive"))
      (node (ref "C18") (pin "2") (pinfunction "2_2") (pintype "passive"))
      (node (ref "C19") (pin "2") (pinfunction "2_2") (pintype "passive"))
      (node (ref "C2") (pin "2") (pinfunction "2_2") (pintype "passive"))
      (node (ref "C20") (pin "2") (pinfunction "2_2") (pintype "passive"))
      (node (ref "C21") (pin "2") (pinfunction "2_2") (pintype "passive"))
      (node (ref "C22") (pin "2") (pinfunction "2_2") (pintype "passive"))
      (node (ref "C23") (pin "2") (pinfunction "2_2") (pintype "passive"))
      (node (ref "C24") (pin "2") (pinfunction "2_2") (pintype "passive"))
      (node (ref "C25") (pin "2") (pinfunction "2_2") (pintype "passive"))
      (node (ref "C26") (pin "2") (pinfunction "2_2") (pintype "passive"))
      (node (ref "C27") (pin "2") (pinfunction "2_2") (pintype "passive"))
      (node (ref "C28") (pin "2") (pinfunction "2_2") (pintype "passive"))
      (node (ref "C3") (pin "2") (pinfunction "2_2") (pintype "passive"))
      (node (ref "C4") (pin "2") (pinfunction "2_2") (pintype "passive"))
      (node (ref "C5") (pin "2") (pinfunction "2_2") (pintype "passive"))
      (node (ref "C6") (pin "2") (pinfunction "2_2") (pintype "passive"))
      (node (ref "C8") (pin "2") (pinfunction "2_2") (pintype "passive"))
      (node (ref "C9") (pin "2") (pinfunction "2_2") (pintype "passive"))
      (node (ref "H1") (pin "GND") (pinfunction "GND_GND") (pintype "passive"))
      (node (ref "H2") (pin "GND") (pinfunction "GND_GND") (pintype "passive"))
      (node (ref "H3") (pin "GND") (pinfunction "GND_GND") (pintype "passive"))
      (node (ref "H4") (pin "GND") (pinfunction "GND_GND") (pintype "passive"))
      (node (ref "P8") (pin "1") (pinfunction "1_1") (pintype "passive"))
      (node (ref "P8") (pin "2") (pinfunction "2_2") (pintype "passive"))
      (node (ref "P9") (pin "1") (pinfunction "1_1") (pintype "passive"))
      (node (ref "P9") (pin "2") (pinfunction "2_2") (pintype "passive"))
      (node (ref "P9") (pin "43") (pinfunction "43_43") (pintype "passive"))
      (node (ref "P9") (pin "44") (pinfunction "44_44") (pintype "passive"))
      (node (ref "P9") (pin "45") (pinfunction "45_45") (pintype "passive"))
      (node (ref "P9") (pin "46") (pinfunction "46_46") (pintype "passive"))
      (node (ref "R33") (pin "1") (pinfunction "1_1") (pintype "passive"))
      (node (ref "R34") (pin "1") (pinfunction "1_1") (pintype "passive"))
      (node (ref "R36") (pin "2") (pinfunction "2_2") (pintype "passive"))
      (node (ref "R4") (pin "1") (pinfunction "1_1") (pintype "passive"))
      (node (ref "S1") (pin "1") (pinfunction "1_1") (pintype "passive"))
      (node (ref "S1") (pin "2") (pinfunction "2_2") (pintype "passive"))
      (node (ref "U$1") (pin "4") (pinfunction "VSS_4") (pintype "power_in"))
      (node (ref "U$10") (pin "2") (pinfunction "GND_2") (pintype "power_in"))
      (node (ref "U$12") (pin "2") (pinfunction "GND_2") (pintype "power_in"))
      (node (ref "U$13") (pin "1") (pinfunction "1DIR_1") (pintype "input"))
      (node (ref "U$13") (pin "10") (pinfunction "GND_10") (pintype "power_in"))
      (node (ref "U$13") (pin "15") (pinfunction "GND_15") (pintype "power_in"))
      (node (ref "U$13") (pin "19") (pinfunction "2B5_19") (pintype "bidirectional"))
      (node (ref "U$13") (pin "20") (pinfunction "2B6_20") (pintype "bidirectional"))
      (node (ref "U$13") (pin "21") (pinfunction "GND_21") (pintype "power_in"))
      (node (ref "U$13") (pin "22") (pinfunction "2B7_22") (pintype "bidirectional"))
      (node (ref "U$13") (pin "23") (pinfunction "2B8_23") (pintype "bidirectional"))
      (node (ref "U$13") (pin "24") (pinfunction "2DIR_24") (pintype "input"))
      (node (ref "U$13") (pin "28") (pinfunction "GND_28") (pintype "power_in"))
      (node (ref "U$13") (pin "34") (pinfunction "GND_34") (pintype "power_in"))
      (node (ref "U$13") (pin "39") (pinfunction "GND_39") (pintype "power_in"))
      (node (ref "U$13") (pin "4") (pinfunction "GND_4") (pintype "power_in"))
      (node (ref "U$13") (pin "45") (pinfunction "GND_45") (pintype "power_in"))
      (node (ref "U$3") (pin "5") (pinfunction "IOVSS_5") (pintype "power_in"))
      (node (ref "U$3") (pin "7") (pinfunction "DVSS_7") (pintype "power_in"))
      (node (ref "U$4") (pin "2") (pinfunction "GND_2") (pintype "power_in"))
      (node (ref "U$5") (pin "10") (pinfunction "GND_10") (pintype "power_in"))
      (node (ref "U$5") (pin "11") (pinfunction "GND_11") (pintype "power_in"))
      (node (ref "U$5") (pin "7") (pinfunction "GND_7") (pintype "power_in"))
      (node (ref "U$7") (pin "1") (pinfunction "GND_1") (pintype "power_in"))
      (node (ref "U$7") (pin "2") (pinfunction "GND_2") (pintype "power_in"))
      (node (ref "U$7") (pin "27") (pinfunction "SD0_A/SA0_27") (pintype "bidirectional"))
      (node (ref "U$7") (pin "3") (pinfunction "GND_3") (pintype "power_in"))
      (node (ref "U$7") (pin "4") (pinfunction "GND_4") (pintype "power_in"))
      (node (ref "U$7") (pin "5") (pinfunction "GND_5") (pintype "power_in"))
      (node (ref "U$7") (pin "6") (pinfunction "GND_6") (pintype "power_in"))
      (node (ref "U$8") (pin "1") (pinfunction "GND_1") (pintype "power_in"))
      (node (ref "U$8") (pin "2") (pinfunction "GND_2") (pintype "power_in"))
      (node (ref "U$8") (pin "26") (pinfunction "SDO_G/SA0_26") (pintype "bidirectional"))
      (node (ref "U$8") (pin "3") (pinfunction "GND_3") (pintype "power_in"))
      (node (ref "U$8") (pin "4") (pinfunction "GND_4") (pintype "power_in"))
      (node (ref "U$8") (pin "6") (pinfunction "GND_6") (pintype "power_in"))
      (node (ref "U$8") (pin "7") (pinfunction "GND_7") (pintype "power_in"))
    )
    (net (code "93") (name "Net-(LED1-PadC)") (class "Default")
      (node (ref "LED1") (pin "C") (pinfunction "C_C") (pintype "passive"))
      (node (ref "R33") (pin "2") (pinfunction "2_2") (pintype "passive"))
    )
    (net (code "94") (name "Net-(LED2-PadC)") (class "Default")
      (node (ref "LED2") (pin "C") (pinfunction "C_C") (pintype "passive"))
      (node (ref "R34") (pin "2") (pinfunction "2_2") (pintype "passive"))
    )
    (net (code "95") (name "Net-(LED3-PadC)") (class "Default")
      (node (ref "LED3") (pin "C") (pinfunction "C_C") (pintype "passive"))
      (node (ref "R35") (pin "2") (pinfunction "2_2") (pintype "passive"))
    )
    (net (code "96") (name "Net-(U$1-A0)") (class "Default")
      (node (ref "R7") (pin "1") (pinfunction "1_1") (pintype "passive"))
      (node (ref "S1") (pin "4") (pinfunction "4_4") (pintype "passive"))
      (node (ref "U$1") (pin "1") (pinfunction "A0_1") (pintype "input"))
    )
    (net (code "97") (name "Net-(U$1-A1)") (class "Default")
      (node (ref "R2") (pin "1") (pinfunction "1_1") (pintype "passive"))
      (node (ref "S1") (pin "3") (pinfunction "3_3") (pintype "passive"))
      (node (ref "U$1") (pin "2") (pinfunction "A1_2") (pintype "input"))
    )
    (net (code "98") (name "Net-(U$1-A2)") (class "Default")
      (node (ref "R4") (pin "2") (pinfunction "2_2") (pintype "passive"))
      (node (ref "R5") (pin "1") (pinfunction "1_1") (pintype "passive"))
      (node (ref "U$1") (pin "3") (pinfunction "A2_3") (pintype "input"))
    )
    (net (code "99") (name "Net-(U$1-WP)") (class "Default")
      (node (ref "R9") (pin "1") (pinfunction "1_1") (pintype "passive"))
      (node (ref "TP1") (pin "TP") (pinfunction "TP_TP") (pintype "input"))
      (node (ref "U$1") (pin "7") (pinfunction "WP_7") (pintype "input"))
    )
    (net (code "100") (name "Net-(U$3-DCLK)") (class "Default")
      (node (ref "R19") (pin "2") (pinfunction "2_2") (pintype "passive"))
      (node (ref "U$3") (pin "10") (pinfunction "DCLK_10") (pintype "output"))
    )
    (net (code "101") (name "Net-(U$3-DOUT0)") (class "Default")
      (node (ref "R6") (pin "2") (pinfunction "2_2") (pintype "passive"))
      (node (ref "U$3") (pin "1") (pinfunction "DOUT0_1") (pintype "output"))
    )
    (net (code "102") (name "Net-(U$3-DOUT1)") (class "Default")
      (node (ref "R8") (pin "2") (pinfunction "2_2") (pintype "passive"))
      (node (ref "U$3") (pin "2") (pinfunction "DOUT1_2") (pintype "output"))
    )
    (net (code "103") (name "Net-(U$3-DOUT2)") (class "Default")
      (node (ref "R10") (pin "2") (pinfunction "2_2") (pintype "passive"))
      (node (ref "U$3") (pin "3") (pinfunction "DOUT2_3") (pintype "output"))
    )
    (net (code "104") (name "Net-(U$3-DOUT3)") (class "Default")
      (node (ref "R11") (pin "2") (pinfunction "2_2") (pintype "passive"))
      (node (ref "U$3") (pin "4") (pinfunction "DOUT3_4") (pintype "output"))
    )
    (net (code "105") (name "Net-(U$3-DOUT4)") (class "Default")
      (node (ref "R12") (pin "2") (pinfunction "2_2") (pintype "passive"))
      (node (ref "U$3") (pin "17") (pinfunction "DOUT4_17") (pintype "output"))
    )
    (net (code "106") (name "Net-(U$3-DOUT5)") (class "Default")
      (node (ref "R13") (pin "2") (pinfunction "2_2") (pintype "passive"))
      (node (ref "U$3") (pin "18") (pinfunction "DOUT5_18") (pintype "output"))
    )
    (net (code "107") (name "Net-(U$3-DOUT6)") (class "Default")
      (node (ref "R14") (pin "2") (pinfunction "2_2") (pintype "passive"))
      (node (ref "U$3") (pin "19") (pinfunction "DOUT6_19") (pintype "output"))
    )
    (net (code "108") (name "Net-(U$3-DOUT7)") (class "Default")
      (node (ref "R15") (pin "2") (pinfunction "2_2") (pintype "passive"))
      (node (ref "U$3") (pin "20") (pinfunction "DOUT7_20") (pintype "output"))
    )
    (net (code "109") (name "Net-(U$3-EXTCLK)") (class "Default")
      (node (ref "R38") (pin "1") (pinfunction "1_1") (pintype "passive"))
      (node (ref "U$3") (pin "12") (pinfunction "EXTCLK_12") (pintype "input"))
    )
    (net (code "110") (name "Net-(U$3-HD)") (class "Default")
      (node (ref "R17") (pin "2") (pinfunction "2_2") (pintype "passive"))
      (node (ref "U$3") (pin "9") (pinfunction "HD_9") (pintype "output"))
    )
    (net (code "111") (name "Net-(U$3-RESET)") (class "Default")
      (node (ref "R18") (pin "2") (pinfunction "2_2") (pintype "passive"))
      (node (ref "R36") (pin "1") (pinfunction "1_1") (pintype "passive"))
      (node (ref "U$3") (pin "13") (pinfunction "RESET_13") (pintype "input"))
    )
    (net (code "112") (name "Net-(U$3-VD)") (class "Default")
      (node (ref "R16") (pin "2") (pinfunction "2_2") (pintype "passive"))
      (node (ref "U$3") (pin "8") (pinfunction "VD_8") (pintype "output"))
    )
    (net (code "113") (name "Net-(U$4-A)") (class "Default")
      (node (ref "R37") (pin "2") (pinfunction "2_2") (pintype "passive"))
      (node (ref "U$4") (pin "3") (pinfunction "A_3") (pintype "bidirectional"))
    )
    (net (code "114") (name "Net-(U$4-B)") (class "Default")
      (node (ref "R38") (pin "2") (pinfunction "2_2") (pintype "passive"))
      (node (ref "U$4") (pin "4") (pinfunction "B_4") (pintype "bidirectional"))
    )
    (net (code "115") (name "Net-(U$5-C1)") (class "Default")
      (node (ref "C5") (pin "1") (pinfunction "1_1") (pintype "passive"))
      (node (ref "U$5") (pin "6") (pinfunction "C1_6") (pintype "passive"))
    )
    (net (code "116") (name "Net-(U$5-SETC)") (class "Default")
      (node (ref "C7") (pin "2") (pinfunction "2_2") (pintype "passive"))
      (node (ref "U$5") (pin "13") (pinfunction "SETC_13") (pintype "passive"))
    )
    (net (code "117") (name "Net-(U$5-SETP)") (class "Default")
      (node (ref "C7") (pin "1") (pinfunction "1_1") (pintype "passive"))
      (node (ref "U$5") (pin "12") (pinfunction "SETP_12") (pintype "passive"))
    )
    (net (code "118") (name "Net-(U$7-CAP)") (class "Default")
      (node (ref "C16") (pin "1") (pinfunction "1_1") (pintype "passive"))
      (node (ref "U$7") (pin "15") (pinfunction "CAP_15") (pintype "passive"))
    )
    (net (code "119") (name "Net-(U$8-C1)") (class "Default")
      (node (ref "C12") (pin "1") (pinfunction "1_1") (pintype "passive"))
      (node (ref "U$8") (pin "5") (pinfunction "C1_5") (pintype "passive"))
    )
    (net (code "120") (name "Net-(U$8-SETC)") (class "Default")
      (node (ref "C11") (pin "1") (pinfunction "1_1") (pintype "passive"))
      (node (ref "U$8") (pin "13") (pinfunction "SETC_13") (pintype "passive"))
    )
    (net (code "121") (name "Net-(U$8-SETP)") (class "Default")
      (node (ref "C11") (pin "2") (pinfunction "2_2") (pintype "passive"))
      (node (ref "C12") (pin "2") (pinfunction "2_2") (pintype "passive"))
      (node (ref "U$8") (pin "14") (pinfunction "SETP_14") (pintype "passive"))
    )
    (net (code "122") (name "Net-(U$10-BYPASS)") (class "Default")
      (node (ref "C18") (pin "1") (pinfunction "1_1") (pintype "passive"))
      (node (ref "U$10") (pin "4") (pinfunction "BYPASS_4") (pintype "passive"))
    )
    (net (code "123") (name "Net-(U$12-NR)") (class "Default")
      (node (ref "C21") (pin "1") (pinfunction "1_1") (pintype "passive"))
      (node (ref "U$12") (pin "4") (pinfunction "NR_4") (pintype "passive"))
    )
    (net (code "124") (name "Net-(U$13-1A1)") (class "Default")
      (node (ref "R20") (pin "2") (pinfunction "2_2") (pintype "passive"))
      (node (ref "U$13") (pin "47") (pinfunction "1A1_47") (pintype "bidirectional"))
    )
    (net (code "125") (name "Net-(U$13-1A2)") (class "Default")
      (node (ref "R21") (pin "2") (pinfunction "2_2") (pintype "passive"))
      (node (ref "U$13") (pin "46") (pinfunction "1A2_46") (pintype "bidirectional"))
    )
    (net (code "126") (name "Net-(U$13-1A3)") (class "Default")
      (node (ref "R22") (pin "2") (pinfunction "2_2") (pintype "passive"))
      (node (ref "U$13") (pin "44") (pinfunction "1A3_44") (pintype "bidirectional"))
    )
    (net (code "127") (name "Net-(U$13-1A4)") (class "Default")
      (node (ref "R23") (pin "2") (pinfunction "2_2") (pintype "passive"))
      (node (ref "U$13") (pin "43") (pinfunction "1A4_43") (pintype "bidirectional"))
    )
    (net (code "128") (name "Net-(U$13-1A5)") (class "Default")
      (node (ref "R24") (pin "2") (pinfunction "2_2") (pintype "passive"))
      (node (ref "U$13") (pin "41") (pinfunction "1A5_41") (pintype "bidirectional"))
    )
    (net (code "129") (name "Net-(U$13-1A6)") (class "Default")
      (node (ref "R25") (pin "2") (pinfunction "2_2") (pintype "passive"))
      (node (ref "U$13") (pin "40") (pinfunction "1A6_40") (pintype "bidirectional"))
    )
    (net (code "130") (name "Net-(U$13-1A7)") (class "Default")
      (node (ref "R26") (pin "2") (pinfunction "2_2") (pintype "passive"))
      (node (ref "U$13") (pin "38") (pinfunction "1A7_38") (pintype "bidirectional"))
    )
    (net (code "131") (name "Net-(U$13-1A8)") (class "Default")
      (node (ref "R27") (pin "2") (pinfunction "2_2") (pintype "passive"))
      (node (ref "U$13") (pin "37") (pinfunction "1A8_37") (pintype "bidirectional"))
    )
    (net (code "132") (name "Net-(U$13-1B1)") (class "Default")
      (node (ref "R6") (pin "1") (pinfunction "1_1") (pintype "passive"))
      (node (ref "U$13") (pin "2") (pinfunction "1B1_2") (pintype "bidirectional"))
    )
    (net (code "133") (name "Net-(U$13-1B2)") (class "Default")
      (node (ref "R8") (pin "1") (pinfunction "1_1") (pintype "passive"))
      (node (ref "U$13") (pin "3") (pinfunction "1B2_3") (pintype "bidirectional"))
    )
    (net (code "134") (name "Net-(U$13-1B3)") (class "Default")
      (node (ref "R10") (pin "1") (pinfunction "1_1") (pintype "passive"))
      (node (ref "U$13") (pin "5") (pinfunction "1B3_5") (pintype "bidirectional"))
    )
    (net (code "135") (name "Net-(U$13-1B4)") (class "Default")
      (node (ref "R11") (pin "1") (pinfunction "1_1") (pintype "passive"))
      (node (ref "U$13") (pin "6") (pinfunction "1B4_6") (pintype "bidirectional"))
    )
    (net (code "136") (name "Net-(U$13-1B5)") (class "Default")
      (node (ref "R12") (pin "1") (pinfunction "1_1") (pintype "passive"))
      (node (ref "U$13") (pin "8") (pinfunction "1B5_8") (pintype "bidirectional"))
    )
    (net (code "137") (name "Net-(U$13-1B6)") (class "Default")
      (node (ref "R13") (pin "1") (pinfunction "1_1") (pintype "passive"))
      (node (ref "U$13") (pin "9") (pinfunction "1B6_9") (pintype "bidirectional"))
    )
    (net (code "138") (name "Net-(U$13-1B7)") (class "Default")
      (node (ref "R14") (pin "1") (pinfunction "1_1") (pintype "passive"))
      (node (ref "U$13") (pin "11") (pinfunction "1B7_11") (pintype "bidirectional"))
    )
    (net (code "139") (name "Net-(U$13-1B8)") (class "Default")
      (node (ref "R15") (pin "1") (pinfunction "1_1") (pintype "passive"))
      (node (ref "U$13") (pin "12") (pinfunction "1B8_12") (pintype "bidirectional"))
    )
    (net (code "140") (name "Net-(U$13-2A1)") (class "Default")
      (node (ref "R28") (pin "2") (pinfunction "2_2") (pintype "passive"))
      (node (ref "U$13") (pin "36") (pinfunction "2A1_36") (pintype "bidirectional"))
    )
    (net (code "141") (name "Net-(U$13-2A2)") (class "Default")
      (node (ref "R29") (pin "2") (pinfunction "2_2") (pintype "passive"))
      (node (ref "U$13") (pin "35") (pinfunction "2A2_35") (pintype "bidirectional"))
    )
    (net (code "142") (name "Net-(U$13-2A4)") (class "Default")
      (node (ref "R31") (pin "2") (pinfunction "2_2") (pintype "passive"))
      (node (ref "U$13") (pin "32") (pinfunction "2A4_32") (pintype "bidirectional"))
    )
    (net (code "143") (name "Net-(U$13-2B1)") (class "Default")
      (node (ref "R16") (pin "1") (pinfunction "1_1") (pintype "passive"))
      (node (ref "U$13") (pin "13") (pinfunction "2B1_13") (pintype "bidirectional"))
    )
    (net (code "144") (name "Net-(U$13-2B2)") (class "Default")
      (node (ref "R17") (pin "1") (pinfunction "1_1") (pintype "passive"))
      (node (ref "U$13") (pin "14") (pinfunction "2B2_14") (pintype "bidirectional"))
    )
    (net (code "145") (name "Net-(U$13-2B4)") (class "Default")
      (node (ref "R19") (pin "1") (pinfunction "1_1") (pintype "passive"))
      (node (ref "U$13") (pin "17") (pinfunction "2B4_17") (pintype "bidirectional"))
    )
    (net (code "146") (name "VDD") (class "Default")
      (node (ref "P9") (pin "5") (pinfunction "5_5") (pintype "passive"))
      (node (ref "P9") (pin "6") (pinfunction "6_6") (pintype "passive"))
    )
    (net (code "147") (name "unconnected-(U$5-INT2-Pad4)") (class "Default")
      (node (ref "U$5") (pin "4") (pinfunction "INT2_4") (pintype "output"))
    )
    (net (code "148") (name "unconnected-(U$7-DRDY_G{slash}INT2_G-Pad17)") (class "Default")
      (node (ref "U$7") (pin "17") (pinfunction "DRDY_G/INT2_G_17") (pintype "output"))
    )
    (net (code "149") (name "unconnected-(U$7-INT2_A-Pad19)") (class "Default")
      (node (ref "U$7") (pin "19") (pinfunction "INT2_A_19") (pintype "output"))
    )
    (net (code "150") (name "unconnected-(U$8-DRDY_G{slash}INT2_G-Pad18)") (class "Default")
      (node (ref "U$8") (pin "18") (pinfunction "DRDY_G/INT2_G_18") (pintype "output"))
    )
    (net (code "151") (name "unconnected-(U$8-INT2_A{slash}M-Pad19)") (class "Default")
      (node (ref "U$8") (pin "19") (pinfunction "INT2_A/M_19") (pintype "output"))
    )
    (net (code "152") (name "unconnected-(U$13-2A3-Pad33)") (class "Default")
      (node (ref "U$13") (pin "33") (pinfunction "2A3_33") (pintype "bidirectional"))
    )
    (net (code "153") (name "unconnected-(U$13-2A5-Pad30)") (class "Default")
      (node (ref "U$13") (pin "30") (pinfunction "2A5_30") (pintype "bidirectional"))
    )
    (net (code "154") (name "unconnected-(U$13-2A6-Pad29)") (class "Default")
      (node (ref "U$13") (pin "29") (pinfunction "2A6_29") (pintype "bidirectional"))
    )
    (net (code "155") (name "unconnected-(U$13-2A7-Pad27)") (class "Default")
      (node (ref "U$13") (pin "27") (pinfunction "2A7_27") (pintype "bidirectional"))
    )
    (net (code "156") (name "unconnected-(U$13-2A8-Pad26)") (class "Default")
      (node (ref "U$13") (pin "26") (pinfunction "2A8_26") (pintype "bidirectional"))
    )
    (net (code "157") (name "unconnected-(U$13-2B3-Pad16)") (class "Default")
      (node (ref "U$13") (pin "16") (pinfunction "2B3_16") (pintype "bidirectional"))
    )
  )
)
